# tof.net
KiCad netlist of a schematic drawn in Altium Designer
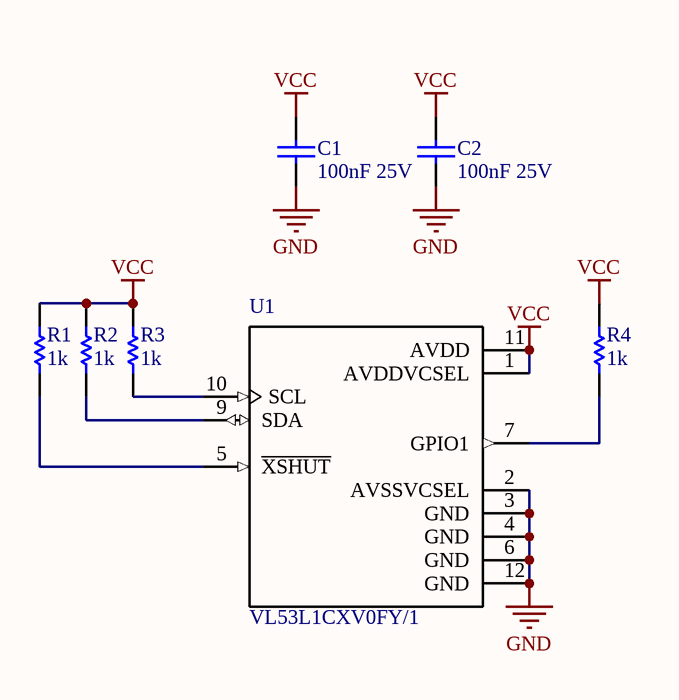
[diagram p0: tof.SchDoc]

(export (version "E")
  (design (tool "Eeschema 10.0.6"))
  (components
    (comp (ref "C1")
      (value "100nF 25V")
      (footprint "RC_0603")
      (description "CAPACITOR CHIP")
      (fields (field (name "MANUFACTURER") "KEMET"))
      (libsource (lib "RozumLibrary") (part "CAP-0603-104-25V"))
    )
    (comp (ref "C2")
      (value "100nF 25V")
      (footprint "RC_0603")
      (description "CAPACITOR CHIP")
      (fields (field (name "MANUFACTURER") "KEMET"))
      (libsource (lib "RozumLibrary") (part "CAP-0603-104-25V"))
    )
    (comp (ref "R1")
      (value "1k")
      (footprint "rr_0603")
      (description "Resistor")
      (fields (field (name "MANUFACTURER") "Yageo"))
      (libsource (lib "Miscellaneous Devices") (part "Res1"))
    )
    (comp (ref "R2")
      (value "1k")
      (footprint "rr_0603")
      (description "Resistor")
      (fields (field (name "MANUFACTURER") "Yageo"))
      (libsource (lib "Miscellaneous Devices") (part "Res1"))
    )
    (comp (ref "R3")
      (value "1k")
      (footprint "rr_0603")
      (description "Resistor")
      (fields (field (name "MANUFACTURER") "Yageo"))
      (libsource (lib "Miscellaneous Devices") (part "Res1"))
    )
    (comp (ref "R4")
      (value "1k")
      (footprint "rr_0603")
      (description "Resistor")
      (fields (field (name "MANUFACTURER") "Yageo"))
      (libsource (lib "Miscellaneous Devices") (part "Res1"))
    )
    (comp (ref "U1")
      (value "VL53L1CXV0FY/1")
      (footprint "*SENSOR_VL53L1CXV0FY/1")
      (description "Optical Sensor 157.480 _4m_ IВІC Output")
      (fields (field (name "MF") "STMicroelectronics"))
      (libsource (lib "VL53L1CXV0FY_1") (part "VL53L1CXV0FY/1"))
    )
  )
  (nets
    (net (code "1") (name "GND") (class "Default")
      (node (ref "C1") (pin "1") (pinfunction "1_1") (pintype "passive"))
      (node (ref "C2") (pin "1") (pinfunction "1_1") (pintype "passive"))
      (node (ref "U1") (pin "12") (pinfunction "GND_12") (pintype "power_in"))
      (node (ref "U1") (pin "2") (pinfunction "AVSSVCSEL_2") (pintype "power_in"))
      (node (ref "U1") (pin "3") (pinfunction "GND_3") (pintype "power_in"))
      (node (ref "U1") (pin "4") (pinfunction "GND_4") (pintype "power_in"))
      (node (ref "U1") (pin "6") (pinfunction "GND_6") (pintype "power_in"))
    )
    (net (code "2") (name "Net-(U1-GPIO1)") (class "Default")
      (node (ref "R4") (pin "1") (pinfunction "1_1") (pintype "passive"))
      (node (ref "U1") (pin "7") (pinfunction "GPIO1_7") (pintype "output"))
    )
    (net (code "3") (name "Net-(U1-SCL)") (class "Default")
      (node (ref "R3") (pin "1") (pinfunction "1_1") (pintype "passive"))
      (node (ref "U1") (pin "10") (pinfunction "SCL_10") (pintype "input"))
    )
    (net (code "4") (name "Net-(U1-SDA)") (class "Default")
      (node (ref "R2") (pin "1") (pinfunction "1_1") (pintype "passive"))
      (node (ref "U1") (pin "9") (pinfunction "SDA_9") (pintype "bidirectional"))
    )
    (net (code "5") (name "Net-(U1-~{XSHUT})") (class "Default")
      (node (ref "R1") (pin "1") (pinfunction "1_1") (pintype "passive"))
      (node (ref "U1") (pin "5") (pinfunction "~{XSHUT}_5") (pintype "input"))
    )
    (net (code "6") (name "VCC") (class "Default")
      (node (ref "C1") (pin "2") (pinfunction "2_2") (pintype "passive"))
      (node (ref "C2") (pin "2") (pinfunction "2_2") (pintype "passive"))
      (node (ref "R1") (pin "2") (pinfunction "2_2") (pintype "passive"))
      (node (ref "R2") (pin "2") (pinfunction "2_2") (pintype "passive"))
      (node (ref "R3") (pin "2") (pinfunction "2_2") (pintype "passive"))
      (node (ref "R4") (pin "2") (pinfunction "2_2") (pintype "passive"))
      (node (ref "U1") (pin "1") (pinfunction "AVDDVCSEL_1") (pintype "power_in"))
      (node (ref "U1") (pin "11") (pinfunction "AVDD_11") (pintype "power_in"))
    )
  )
)
